# enkoder.net
KiCad netlist of a schematic drawn in EAGLE
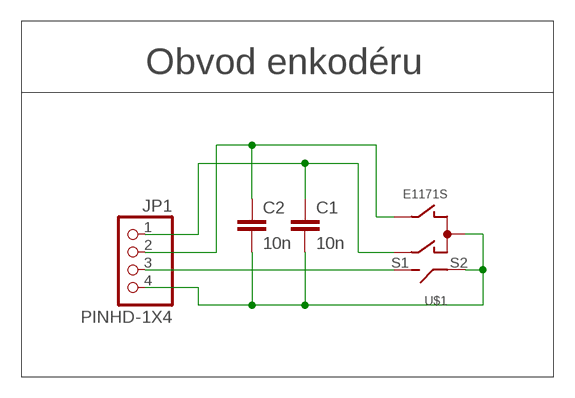
[diagram p0: schematic, sheet 1]

(export (version "E")
  (design (tool "Eeschema 10.0.6"))
  (components
    (comp (ref "C1")
      (value "10n")
      (footprint "eagle-import:C0805")
      (libsource (lib "eagle-import") (part "C-EUC0805"))
    )
    (comp (ref "C2")
      (value "10n")
      (footprint "eagle-import:C0805")
      (libsource (lib "eagle-import") (part "C-EUC0805"))
    )
    (comp (ref "JP1")
      (value "PINHD-1X4")
      (footprint "eagle-import:1X04")
      (libsource (lib "eagle-import") (part "PINHD-1X4"))
    )
    (comp (ref "U$1")
      (value "E1171S")
      (footprint "eagle-import:E1171S")
      (libsource (lib "eagle-import") (part "E1171S"))
    )
  )
  (nets
    (net (code "1") (name "Net-(C1-Pad1)") (class "Default")
      (node (ref "C1") (pin "1") (pinfunction "1_1") (pintype "passive"))
      (node (ref "JP1") (pin "1") (pinfunction "1_1") (pintype "passive"))
      (node (ref "U$1") (pin "A") (pinfunction "A_A") (pintype "passive"))
    )
    (net (code "2") (name "Net-(C1-Pad2)") (class "Default")
      (node (ref "C1") (pin "2") (pinfunction "2_2") (pintype "passive"))
      (node (ref "C2") (pin "2") (pinfunction "2_2") (pintype "passive"))
      (node (ref "JP1") (pin "4") (pinfunction "4_4") (pintype "passive"))
      (node (ref "U$1") (pin "C") (pinfunction "C_C") (pintype "passive"))
      (node (ref "U$1") (pin "S2") (pinfunction "S2_S2") (pintype "bidirectional"))
    )
    (net (code "3") (name "Net-(C2-Pad1)") (class "Default")
      (node (ref "C2") (pin "1") (pinfunction "1_1") (pintype "passive"))
      (node (ref "JP1") (pin "2") (pinfunction "2_2") (pintype "passive"))
      (node (ref "U$1") (pin "B") (pinfunction "B_B") (pintype "passive"))
    )
    (net (code "4") (name "Net-(JP1-Pad3)") (class "Default")
      (node (ref "JP1") (pin "3") (pinfunction "3_3") (pintype "passive"))
      (node (ref "U$1") (pin "S1") (pinfunction "S1_S1") (pintype "bidirectional"))
    )
  )
)
